# DDS.net
KiCad netlist of a schematic drawn in Altium Designer
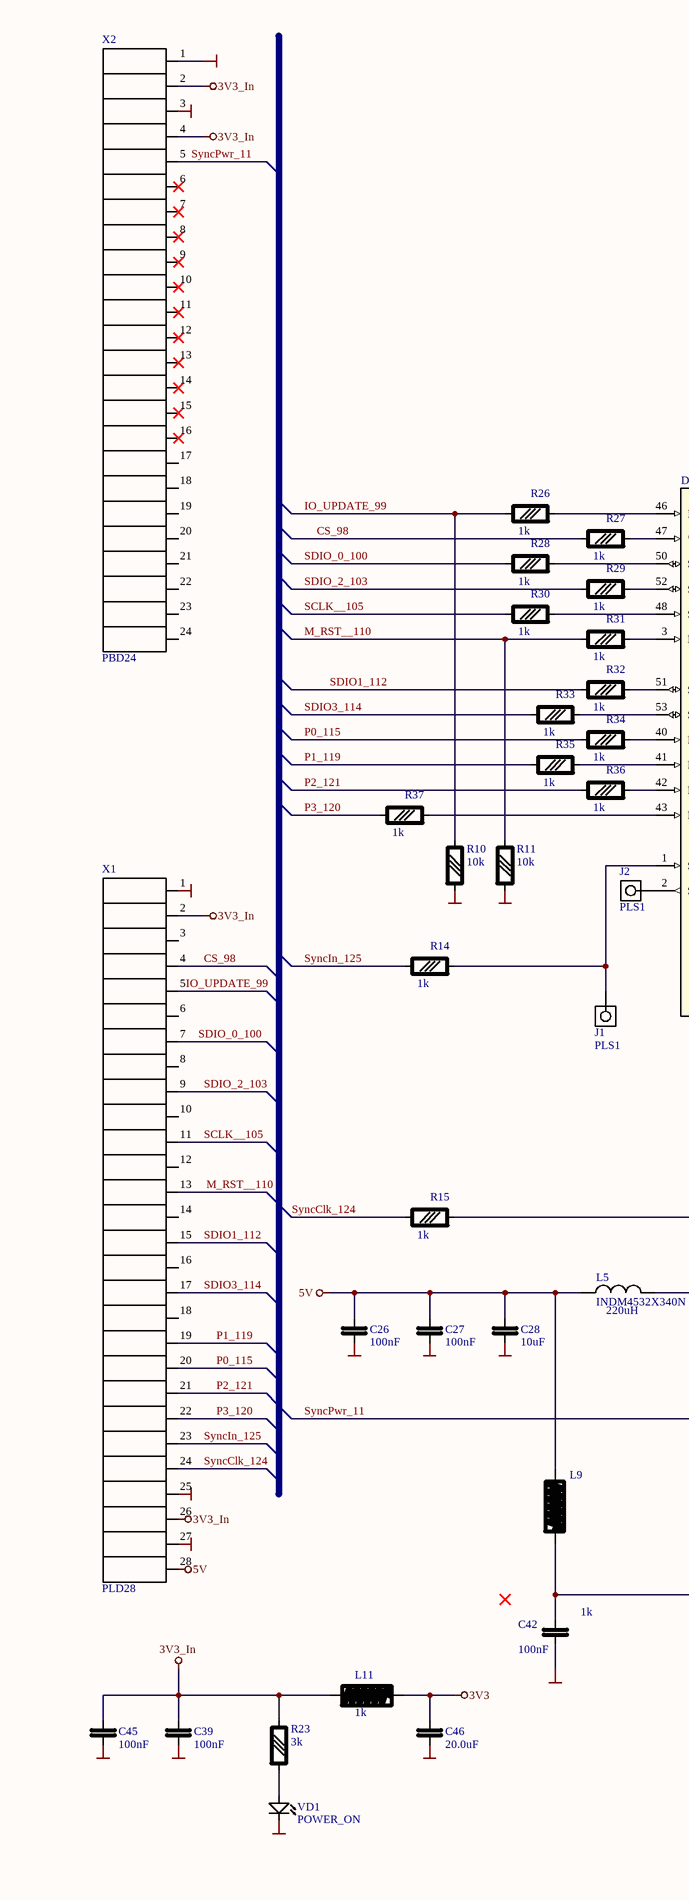
[diagram p0: DDS.SchDoc, left]
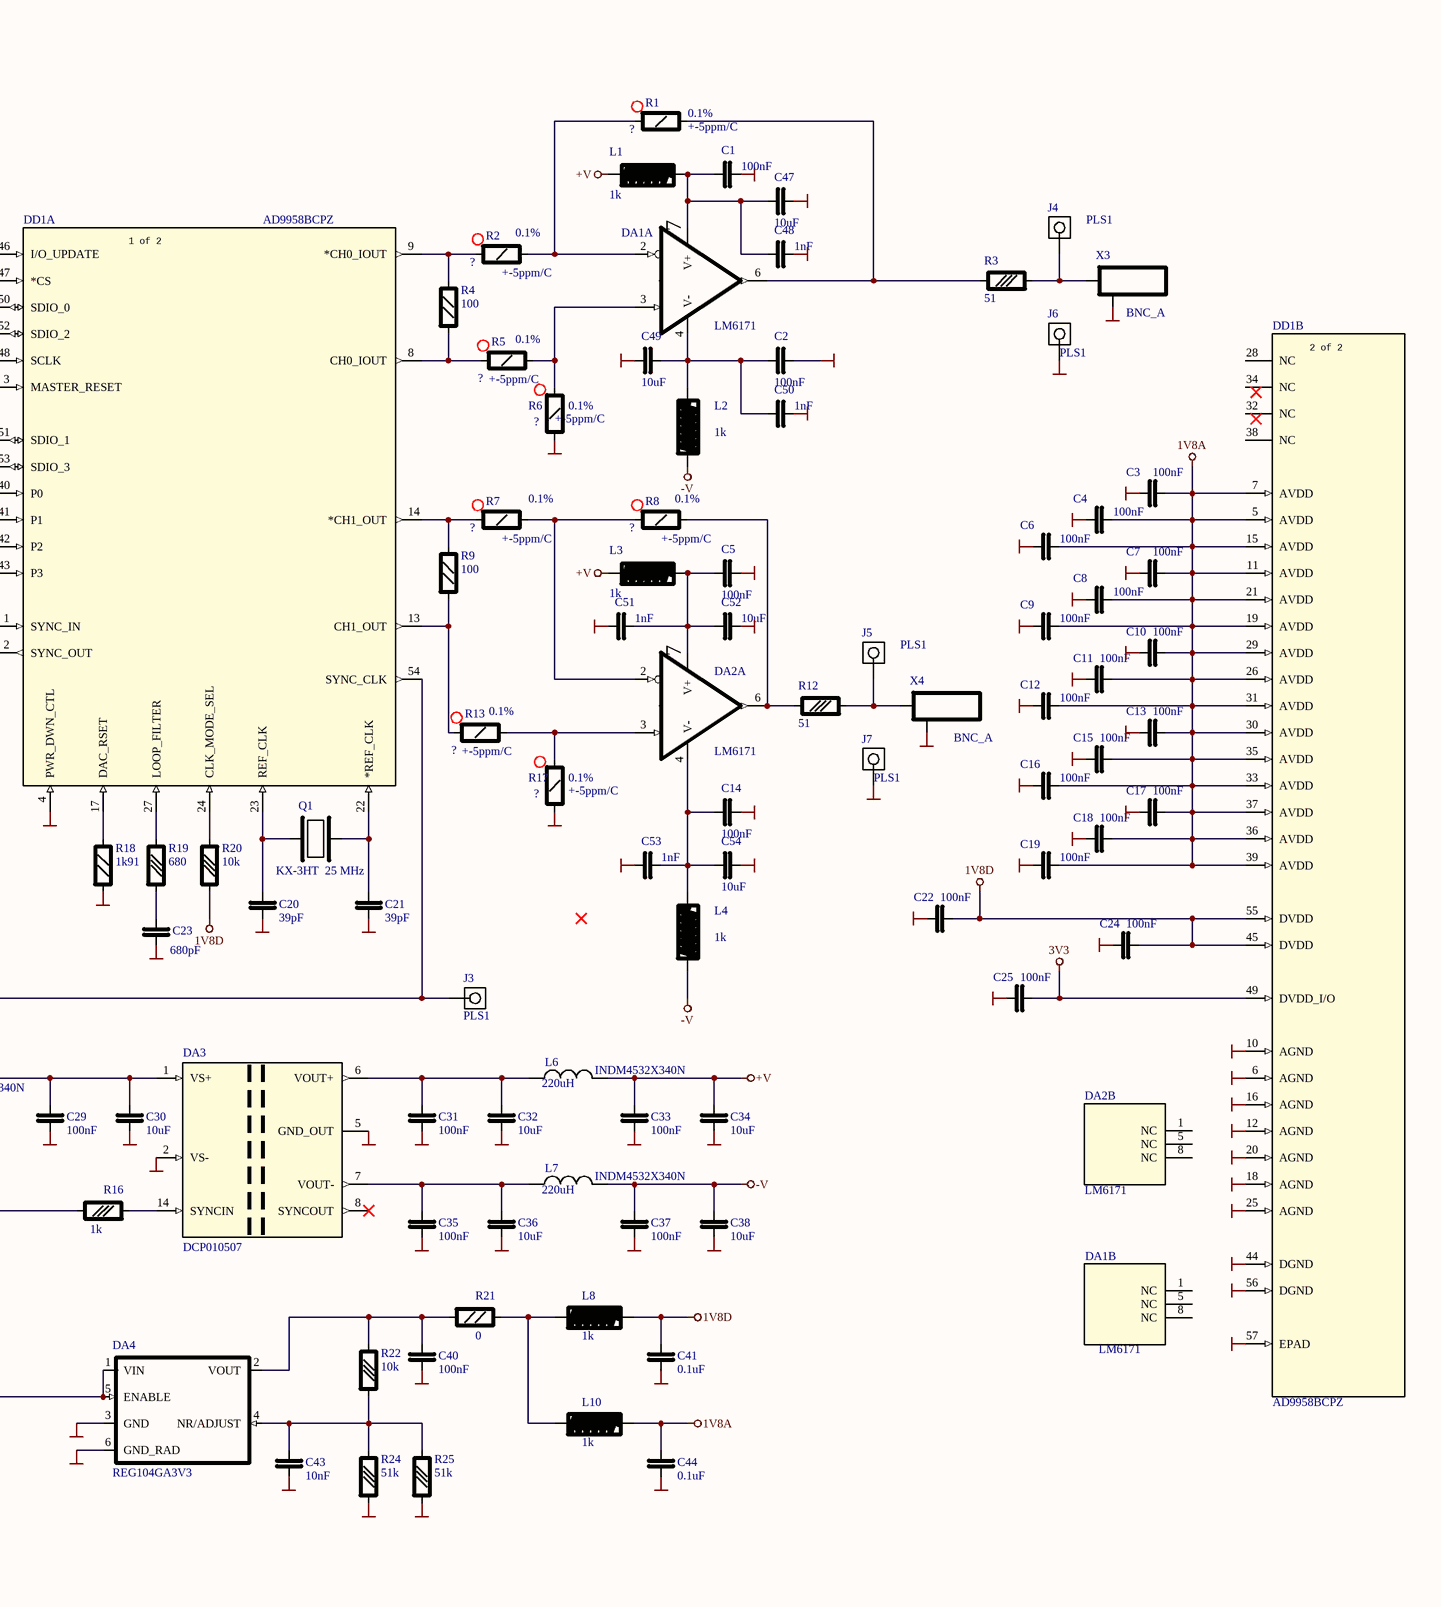
[diagram p1: DDS.SchDoc, right]

(export (version "E")
  (design (tool "Eeschema 10.0.6"))
  (components
    (comp (ref "C1")
      (value "100nF")
      (footprint "CAPC1608X87N")
      (description "Чип конденсатор 0603")
      (fields (field (name "VOLTAGE") "50V"))
      (libsource (lib "iL04_22") (part "C0603"))
    )
    (comp (ref "C2")
      (value "100nF")
      (footprint "CAPC1608X87N")
      (description "Чип конденсатор 0603")
      (fields (field (name "VOLTAGE") "50V"))
      (libsource (lib "iL04_22") (part "C0603"))
    )
    (comp (ref "C3")
      (value "100nF")
      (footprint "CAPC1608X87N")
      (description "Чип конденсатор 0603")
      (fields (field (name "VOLTAGE") "50V"))
      (libsource (lib "iL04_22") (part "C0603"))
    )
    (comp (ref "C4")
      (value "100nF")
      (footprint "CAPC1608X87N")
      (description "Чип конденсатор 0603")
      (fields (field (name "VOLTAGE") "50V"))
      (libsource (lib "iL04_22") (part "C0603"))
    )
    (comp (ref "C5")
      (value "100nF")
      (footprint "CAPC1608X87N")
      (description "Чип конденсатор 0603")
      (fields (field (name "VOLTAGE") "50V"))
      (libsource (lib "iL04_22") (part "C0603"))
    )
    (comp (ref "C6")
      (value "100nF")
      (footprint "CAPC1608X87N")
      (description "Чип конденсатор 0603")
      (fields (field (name "VOLTAGE") "50V"))
      (libsource (lib "iL04_22") (part "C0603"))
    )
    (comp (ref "C7")
      (value "100nF")
      (footprint "CAPC1608X87N")
      (description "Чип конденсатор 0603")
      (fields (field (name "VOLTAGE") "50V"))
      (libsource (lib "iL04_22") (part "C0603"))
    )
    (comp (ref "C8")
      (value "100nF")
      (footprint "CAPC1608X87N")
      (description "Чип конденсатор 0603")
      (fields (field (name "VOLTAGE") "50V"))
      (libsource (lib "iL04_22") (part "C0603"))
    )
    (comp (ref "C9")
      (value "100nF")
      (footprint "CAPC1608X87N")
      (description "Чип конденсатор 0603")
      (fields (field (name "VOLTAGE") "50V"))
      (libsource (lib "iL04_22") (part "C0603"))
    )
    (comp (ref "C10")
      (value "100nF")
      (footprint "CAPC1608X87N")
      (description "Чип конденсатор 0603")
      (fields (field (name "VOLTAGE") "50V"))
      (libsource (lib "iL04_22") (part "C0603"))
    )
    (comp (ref "C11")
      (value "100nF")
      (footprint "CAPC1608X87N")
      (description "Чип конденсатор 0603")
      (fields (field (name "VOLTAGE") "50V"))
      (libsource (lib "iL04_22") (part "C0603"))
    )
    (comp (ref "C12")
      (value "100nF")
      (footprint "CAPC1608X87N")
      (description "Чип конденсатор 0603")
      (fields (field (name "VOLTAGE") "50V"))
      (libsource (lib "iL04_22") (part "C0603"))
    )
    (comp (ref "C13")
      (value "100nF")
      (footprint "CAPC1608X87N")
      (description "Чип конденсатор 0603")
      (fields (field (name "VOLTAGE") "50V"))
      (libsource (lib "iL04_22") (part "C0603"))
    )
    (comp (ref "C14")
      (value "100nF")
      (footprint "CAPC1608X87N")
      (description "Чип конденсатор 0603")
      (fields (field (name "VOLTAGE") "50V"))
      (libsource (lib "iL04_22") (part "C0603"))
    )
    (comp (ref "C15")
      (value "100nF")
      (footprint "CAPC1608X87N")
      (description "Чип конденсатор 0603")
      (fields (field (name "VOLTAGE") "50V"))
      (libsource (lib "iL04_22") (part "C0603"))
    )
    (comp (ref "C16")
      (value "100nF")
      (footprint "CAPC1608X87N")
      (description "Чип конденсатор 0603")
      (fields (field (name "VOLTAGE") "50V"))
      (libsource (lib "iL04_22") (part "C0603"))
    )
    (comp (ref "C17")
      (value "100nF")
      (footprint "CAPC1608X87N")
      (description "Чип конденсатор 0603")
      (fields (field (name "VOLTAGE") "50V"))
      (libsource (lib "iL04_22") (part "C0603"))
    )
    (comp (ref "C18")
      (value "100nF")
      (footprint "CAPC1608X87N")
      (description "Чип конденсатор 0603")
      (fields (field (name "VOLTAGE") "50V"))
      (libsource (lib "iL04_22") (part "C0603"))
    )
    (comp (ref "C19")
      (value "100nF")
      (footprint "CAPC1608X87N")
      (description "Чип конденсатор 0603")
      (fields (field (name "VOLTAGE") "50V"))
      (libsource (lib "iL04_22") (part "C0603"))
    )
    (comp (ref "C20")
      (value "39pF")
      (footprint "CAPC1608X87N")
      (description "Чип конденсатор 0603")
      (fields (field (name "VOLTAGE") "50V"))
      (libsource (lib "iL04_22") (part "C0603"))
    )
    (comp (ref "C21")
      (value "39pF")
      (footprint "CAPC1608X87N")
      (description "Чип конденсатор 0603")
      (fields (field (name "VOLTAGE") "50V"))
      (libsource (lib "iL04_22") (part "C0603"))
    )
    (comp (ref "C22")
      (value "100nF")
      (footprint "CAPC1608X87N")
      (description "Чип конденсатор 0603")
      (fields (field (name "VOLTAGE") "50V"))
      (libsource (lib "iL04_22") (part "C0603"))
    )
    (comp (ref "C23")
      (value "680pF")
      (footprint "CAPC1608X87N")
      (description "Чип конденсатор 0603")
      (fields (field (name "VOLTAGE") "50V"))
      (libsource (lib "iL04_22") (part "C0603"))
    )
    (comp (ref "C24")
      (value "100nF")
      (footprint "CAPC1608X87N")
      (description "Чип конденсатор 0603")
      (fields (field (name "VOLTAGE") "50V"))
      (libsource (lib "iL04_22") (part "C0603"))
    )
    (comp (ref "C25")
      (value "100nF")
      (footprint "CAPC1608X87N")
      (description "Чип конденсатор 0603")
      (fields (field (name "VOLTAGE") "50V"))
      (libsource (lib "iL04_22") (part "C0603"))
    )
    (comp (ref "C26")
      (value "100nF")
      (footprint "CAPC1608X87N")
      (description "Чип конденсатор 0603")
      (fields (field (name "VOLTAGE") "50V"))
      (libsource (lib "iL04_22") (part "C0603"))
    )
    (comp (ref "C27")
      (value "100nF")
      (footprint "CAPC1608X87N")
      (description "Чип конденсатор 0603")
      (fields (field (name "VOLTAGE") "50V"))
      (libsource (lib "iL04_22") (part "C0603"))
    )
    (comp (ref "C28")
      (value "10uF")
      (footprint "SMD0805CAP")
      (description "Чип конденсатор 0805")
      (fields (field (name "VOLTAGE") "50V"))
      (libsource (lib "iL04_22") (part "C0805"))
    )
    (comp (ref "C29")
      (value "100nF")
      (footprint "CAPC1608X87N")
      (description "Чип конденсатор 0603")
      (fields (field (name "VOLTAGE") "50V"))
      (libsource (lib "iL04_22") (part "C0603"))
    )
    (comp (ref "C30")
      (value "10uF")
      (footprint "SMD0805CAP")
      (description "Чип конденсатор 0805")
      (fields (field (name "VOLTAGE") "50V"))
      (libsource (lib "iL04_22") (part "C0805"))
    )
    (comp (ref "C31")
      (value "100nF")
      (footprint "CAPC1608X87N")
      (description "Чип конденсатор 0603")
      (fields (field (name "VOLTAGE") "50V"))
      (libsource (lib "iL04_22") (part "C0603"))
    )
    (comp (ref "C32")
      (value "10uF")
      (footprint "SMD0805CAP")
      (description "Чип конденсатор 0805")
      (fields (field (name "VOLTAGE") "50V"))
      (libsource (lib "iL04_22") (part "C0805"))
    )
    (comp (ref "C33")
      (value "100nF")
      (footprint "CAPC1608X87N")
      (description "Чип конденсатор 0603")
      (fields (field (name "VOLTAGE") "50V"))
      (libsource (lib "iL04_22") (part "C0603"))
    )
    (comp (ref "C34")
      (value "10uF")
      (footprint "SMD0805CAP")
      (description "Чип конденсатор 0805")
      (fields (field (name "VOLTAGE") "50V"))
      (libsource (lib "iL04_22") (part "C0805"))
    )
    (comp (ref "C35")
      (value "100nF")
      (footprint "CAPC1608X87N")
      (description "Чип конденсатор 0603")
      (fields (field (name "VOLTAGE") "50V"))
      (libsource (lib "iL04_22") (part "C0603"))
    )
    (comp (ref "C36")
      (value "10uF")
      (footprint "SMD0805CAP")
      (description "Чип конденсатор 0805")
      (fields (field (name "VOLTAGE") "50V"))
      (libsource (lib "iL04_22") (part "C0805"))
    )
    (comp (ref "C37")
      (value "100nF")
      (footprint "CAPC1608X87N")
      (description "Чип конденсатор 0603")
      (fields (field (name "VOLTAGE") "50V"))
      (libsource (lib "iL04_22") (part "C0603"))
    )
    (comp (ref "C38")
      (value "10uF")
      (footprint "SMD0805CAP")
      (description "Чип конденсатор 0805")
      (fields (field (name "VOLTAGE") "50V"))
      (libsource (lib "iL04_22") (part "C0805"))
    )
    (comp (ref "C39")
      (value "100nF")
      (footprint "CAPC1608X87N")
      (description "Чип конденсатор 0603")
      (fields (field (name "VOLTAGE") "50V"))
      (libsource (lib "iL04_22") (part "C0603"))
    )
    (comp (ref "C40")
      (value "100nF")
      (footprint "CAPC1608X87N")
      (description "Чип конденсатор 0603")
      (fields (field (name "VOLTAGE") "50V"))
      (libsource (lib "iL04_22") (part "C0603"))
    )
    (comp (ref "C41")
      (value "0.1uF")
      (footprint "SMD0805CAP")
      (description "Чип конденсатор 0805")
      (fields (field (name "VOLTAGE") "50V"))
      (libsource (lib "iL04_22") (part "C0805"))
    )
    (comp (ref "C42")
      (value "100nF")
      (footprint "CAPC1608X87N")
      (description "Чип конденсатор 0603")
      (fields (field (name "VOLTAGE") "50V"))
      (libsource (lib "iL04_22") (part "C0603"))
    )
    (comp (ref "C43")
      (value "10nF")
      (footprint "CAPC1608X87N")
      (description "Чип конденсатор 0603")
      (fields (field (name "VOLTAGE") "50V"))
      (libsource (lib "iL04_22") (part "C0603"))
    )
    (comp (ref "C44")
      (value "0.1uF")
      (footprint "SMD0805CAP")
      (description "Чип конденсатор 0805")
      (fields (field (name "VOLTAGE") "50V"))
      (libsource (lib "iL04_22") (part "C0805"))
    )
    (comp (ref "C45")
      (value "100nF")
      (footprint "CAPC1608X87N")
      (description "Чип конденсатор 0603")
      (fields (field (name "VOLTAGE") "50V"))
      (libsource (lib "iL04_22") (part "C0603"))
    )
    (comp (ref "C46")
      (value "20.0uF")
      (footprint "SMD0805CAP")
      (description "Чип конденсатор 0805")
      (fields (field (name "VOLTAGE") "20V"))
      (libsource (lib "iL04_22") (part "C0805"))
    )
    (comp (ref "C47")
      (value "10uF")
      (footprint "CAPC1206")
      (description "Чип конденсатор 0805")
      (fields (field (name "VOLTAGE") "25V"))
      (libsource (lib "iL04_22") (part "C1206"))
    )
    (comp (ref "C48")
      (value "1nF")
      (footprint "CAPC1608X87N")
      (description "Чип конденсатор 0603")
      (fields (field (name "VOLTAGE") "50V"))
      (libsource (lib "iL04_22") (part "C0603"))
    )
    (comp (ref "C49")
      (value "10uF")
      (footprint "CAPC1206")
      (description "Чип конденсатор 0805")
      (fields (field (name "VOLTAGE") "25V"))
      (libsource (lib "iL04_22") (part "C1206"))
    )
    (comp (ref "C50")
      (value "1nF")
      (footprint "CAPC1608X87N")
      (description "Чип конденсатор 0603")
      (fields (field (name "VOLTAGE") "50V"))
      (libsource (lib "iL04_22") (part "C0603"))
    )
    (comp (ref "C51")
      (value "1nF")
      (footprint "CAPC1608X87N")
      (description "Чип конденсатор 0603")
      (fields (field (name "VOLTAGE") "50V"))
      (libsource (lib "iL04_22") (part "C0603"))
    )
    (comp (ref "C52")
      (value "10uF")
      (footprint "CAPC1206")
      (description "Чип конденсатор 0805")
      (fields (field (name "VOLTAGE") "25V"))
      (libsource (lib "iL04_22") (part "C1206"))
    )
    (comp (ref "C53")
      (value "1nF")
      (footprint "CAPC1608X87N")
      (description "Чип конденсатор 0603")
      (fields (field (name "VOLTAGE") "50V"))
      (libsource (lib "iL04_22") (part "C0603"))
    )
    (comp (ref "C54")
      (value "10uF")
      (footprint "CAPC1206")
      (description "Чип конденсатор 0805")
      (fields (field (name "VOLTAGE") "25V"))
      (libsource (lib "iL04_22") (part "C1206"))
    )
    (comp (ref "DA1")
      (value "LM6171")
      (footprint "DIP8-300")
      (description "No Description Available")
      (fields
        (field (name "MANUFACTURER_PART_NUMBER") "LM6171BIN/NOPB")
        (field (name "MANUFACTURER") "Texas Instruments")
      )
      (libsource (lib "SL04_22F") (part "LM6171"))
    )
    (comp (ref "DA2")
      (value "LM6171")
      (footprint "DIP8-300")
      (description "No Description Available")
      (fields
        (field (name "MANUFACTURER_PART_NUMBER") "LM6171BIN/NOPB")
        (field (name "MANUFACTURER") "Texas Instruments")
      )
      (libsource (lib "SL04_22F") (part "LM6171"))
    )
    (comp (ref "DA3")
      (value "DCP010507")
      (footprint "NVA7")
      (description "DC/DC 5V to isolated +-7V")
      (fields (field (name "COPYRIGHT") "Copyright (C) 2022 Ultra Librarian. All rights reserved."))
      (libsource (lib "SL04_22F") (part "DCP010507"))
    )
    (comp (ref "DA4")
      (value "REG104GA3V3")
      (footprint "SOT223_6-127")
      (description "Positive LDO Linear stabilizer")
      (libsource (lib "SL04_22F") (part "REG104GA"))
    )
    (comp (ref "DD1")
      (value "AD9958BCPZ")
      (footprint "CP_56_1_ADI-M")
      (description "2х канальный   500 MSpS  DDS")
      (fields (field (name "VOLTAGE") "Core:1V8 IO:3V3"))
      (libsource (lib "SL04_22F") (part "AD9958BCPZ"))
    )
    (comp (ref "J1")
      (value "PLS1")
      (footprint "PLS1")
      (description "Штырь PLS1")
      (libsource (lib "iL04_22") (part "PLS1"))
    )
    (comp (ref "J2")
      (value "PLS1")
      (footprint "PLS1")
      (description "Штырь PLS1")
      (libsource (lib "iL04_22") (part "PLS1"))
    )
    (comp (ref "J3")
      (value "PLS1")
      (footprint "PLS1")
      (description "Штырь PLS1")
      (libsource (lib "iL04_22") (part "PLS1"))
    )
    (comp (ref "J4")
      (value "PLS1")
      (footprint "PLS1")
      (description "Штырь PLS1")
      (libsource (lib "iL04_22") (part "PLS1"))
    )
    (comp (ref "J5")
      (value "PLS1")
      (footprint "PLS1")
      (description "Штырь PLS1")
      (libsource (lib "iL04_22") (part "PLS1"))
    )
    (comp (ref "J6")
      (value "PLS1")
      (footprint "PLS1")
      (description "Штырь PLS1")
      (libsource (lib "iL04_22") (part "PLS1"))
    )
    (comp (ref "J7")
      (value "PLS1")
      (footprint "PLS1")
      (description "Штырь PLS1")
      (libsource (lib "iL04_22") (part "PLS1"))
    )
    (comp (ref "L1")
      (value "1k")
      (footprint "RESC2012X50N")
      (description "SMD Ferrite bead 0805")
      (libsource (lib "iL04_22") (part "BLM21"))
    )
    (comp (ref "L2")
      (value "1k")
      (footprint "RESC2012X50N")
      (description "SMD Ferrite bead 0805")
      (libsource (lib "") (part "BLM21_1"))
    )
    (comp (ref "L3")
      (value "1k")
      (footprint "RESC2012X50N")
      (description "SMD Ferrite bead 0805")
      (libsource (lib "iL04_22") (part "BLM21"))
    )
    (comp (ref "L4")
      (value "1k")
      (footprint "RESC2012X50N")
      (description "SMD Ferrite bead 0805")
      (libsource (lib "") (part "BLM21_1"))
    )
    (comp (ref "L5")
      (value "INDM4532X340N")
      (footprint "INDM4532X340N")
      (description "SMD Дроссель")
      (fields (field (name "INDUCTANCE") "220uH"))
      (libsource (lib "iL04_22") (part "INDM4532X340N"))
    )
    (comp (ref "L6")
      (value "INDM4532X340N")
      (footprint "INDM4532X340N")
      (description "SMD Дроссель")
      (fields (field (name "INDUCTANCE") "220uH"))
      (libsource (lib "iL04_22") (part "INDM4532X340N"))
    )
    (comp (ref "L7")
      (value "INDM4532X340N")
      (footprint "INDM4532X340N")
      (description "SMD Дроссель")
      (fields (field (name "INDUCTANCE") "220uH"))
      (libsource (lib "iL04_22") (part "INDM4532X340N"))
    )
    (comp (ref "L8")
      (value "1k")
      (footprint "RESC2012X50N")
      (description "SMD Ferrite bead 0805")
      (libsource (lib "iL04_22") (part "BLM21"))
    )
    (comp (ref "L9")
      (value "1k")
      (footprint "RESC2012X50N")
      (description "SMD Ferrite bead 0805")
      (libsource (lib "") (part "BLM21_2"))
    )
    (comp (ref "L10")
      (value "1k")
      (footprint "RESC2012X50N")
      (description "SMD Ferrite bead 0805")
      (libsource (lib "iL04_22") (part "BLM21"))
    )
    (comp (ref "L11")
      (value "1k")
      (footprint "RESC2012X50N")
      (description "SMD Ferrite bead 0805")
      (libsource (lib "iL04_22") (part "BLM21"))
    )
    (comp (ref "Q1")
      (value "KX-3HT  25 MHz")
      (footprint "HC49_S")
      (description "Резонатор кварцевый")
      (libsource (lib "iL04_22") (part "KX-3HT"))
    )
    (comp (ref "R1")
      (value "?")
      (footprint "RES_VISHAY_CMF60")
      (description "Чип резистор 1206")
      (fields (field (name "TOLERANCE") "0.1%") (field (name "TC") "+-5ppm/C"))
      (libsource (lib "iL04_22") (part "S2-29"))
    )
    (comp (ref "R2")
      (value "?")
      (footprint "RES_VISHAY_CMF60")
      (description "Чип резистор 1206")
      (fields (field (name "TOLERANCE") "0.1%") (field (name "TC") "+-5ppm/C"))
      (libsource (lib "iL04_22") (part "S2-29"))
    )
    (comp (ref "R3")
      (value "51")
      (footprint "RESC1608X64N")
      (description "Чип резистор 0603")
      (fields (field (name "TOLERANCE") "5%"))
      (libsource (lib "iL04_22") (part "R0603"))
    )
    (comp (ref "R4")
      (value "100")
      (footprint "SMD0805RES")
      (description "Чип резистор 0805")
      (fields (field (name "TOLERANCE") "5%"))
      (libsource (lib "iL04_22") (part "R0805"))
    )
    (comp (ref "R5")
      (value "?")
      (footprint "RES_VISHAY_CMF60")
      (description "Чип резистор 1206")
      (fields (field (name "TOLERANCE") "0.1%") (field (name "TC") "+-5ppm/C"))
      (libsource (lib "iL04_22") (part "S2-29"))
    )
    (comp (ref "R6")
      (value "?")
      (footprint "RES_VISHAY_CMF60")
      (description "Чип резистор 1206")
      (fields (field (name "TOLERANCE") "0.1%") (field (name "TC") "+-5ppm/C"))
      (libsource (lib "") (part "S2-29_1"))
    )
    (comp (ref "R7")
      (value "?")
      (footprint "RES_VISHAY_CMF60")
      (description "Чип резистор 1206")
      (fields (field (name "TOLERANCE") "0.1%") (field (name "TC") "+-5ppm/C"))
      (libsource (lib "iL04_22") (part "S2-29"))
    )
    (comp (ref "R8")
      (value "?")
      (footprint "RES_VISHAY_CMF60")
      (description "Чип резистор 1206")
      (fields (field (name "TOLERANCE") "0.1%") (field (name "TC") "+-5ppm/C"))
      (libsource (lib "iL04_22") (part "S2-29"))
    )
    (comp (ref "R9")
      (value "100")
      (footprint "SMD0805RES")
      (description "Чип резистор 0805")
      (fields (field (name "TOLERANCE") "5%"))
      (libsource (lib "iL04_22") (part "R0805"))
    )
    (comp (ref "R10")
      (value "10k")
      (footprint "RESC1608X64N")
      (description "Чип резистор 0603")
      (fields (field (name "TOLERANCE") "5%"))
      (libsource (lib "iL04_22") (part "R0603"))
    )
    (comp (ref "R11")
      (value "10k")
      (footprint "RESC1608X64N")
      (description "Чип резистор 0603")
      (fields (field (name "TOLERANCE") "5%"))
      (libsource (lib "iL04_22") (part "R0603"))
    )
    (comp (ref "R12")
      (value "51")
      (footprint "RESC1608X64N")
      (description "Чип резистор 0603")
      (fields (field (name "TOLERANCE") "5%"))
      (libsource (lib "iL04_22") (part "R0603"))
    )
    (comp (ref "R13")
      (value "?")
      (footprint "RES_VISHAY_CMF60")
      (description "Чип резистор 1206")
      (fields (field (name "TOLERANCE") "0.1%") (field (name "TC") "+-5ppm/C"))
      (libsource (lib "iL04_22") (part "S2-29"))
    )
    (comp (ref "R14")
      (value "1k")
      (footprint "RESC1608X64N")
      (description "Чип резистор 0603")
      (fields (field (name "TOLERANCE") "5%"))
      (libsource (lib "iL04_22") (part "R0603"))
    )
    (comp (ref "R15")
      (value "1k")
      (footprint "RESC1608X64N")
      (description "Чип резистор 0603")
      (fields (field (name "TOLERANCE") "5%"))
      (libsource (lib "iL04_22") (part "R0603"))
    )
    (comp (ref "R16")
      (value "1k")
      (footprint "RESC1608X64N")
      (description "Чип резистор 0603")
      (fields (field (name "TOLERANCE") "5%"))
      (libsource (lib "iL04_22") (part "R0603"))
    )
    (comp (ref "R17")
      (value "?")
      (footprint "RES_VISHAY_CMF60")
      (description "Чип резистор 1206")
      (fields (field (name "TOLERANCE") "0.1%") (field (name "TC") "+-5ppm/C"))
      (libsource (lib "") (part "S2-29_1"))
    )
    (comp (ref "R18")
      (value "1k91")
      (footprint "SMD0805RES")
      (description "Чип резистор 0805")
      (fields (field (name "TOLERANCE") "5%"))
      (libsource (lib "iL04_22") (part "R0805"))
    )
    (comp (ref "R19")
      (value "680")
      (footprint "RESC1608X64N")
      (description "Чип резистор 0603")
      (fields (field (name "TOLERANCE") "5%"))
      (libsource (lib "iL04_22") (part "R0603"))
    )
    (comp (ref "R20")
      (value "10k")
      (footprint "RESC1608X64N")
      (description "Чип резистор 0603")
      (fields (field (name "TOLERANCE") "5%"))
      (libsource (lib "iL04_22") (part "R0603"))
    )
    (comp (ref "R21")
      (value "0")
      (footprint "SMD0805RES")
      (description "Чип резистор 0805")
      (fields (field (name "TOLERANCE") "5%"))
      (libsource (lib "iL04_22") (part "R0805"))
    )
    (comp (ref "R22")
      (value "10k")
      (footprint "RESC1608X64N")
      (description "Чип резистор 0603")
      (fields (field (name "TOLERANCE") "5%"))
      (libsource (lib "iL04_22") (part "R0603"))
    )
    (comp (ref "R23")
      (value "3k")
      (footprint "RESC1608X64N")
      (description "Чип резистор 0603")
      (fields (field (name "TOLERANCE") "5%"))
      (libsource (lib "iL04_22") (part "R0603"))
    )
    (comp (ref "R24")
      (value "51k")
      (footprint "RESC1608X64N")
      (description "Чип резистор 0603")
      (fields (field (name "TOLERANCE") "5%"))
      (libsource (lib "iL04_22") (part "R0603"))
    )
    (comp (ref "R25")
      (value "51k")
      (footprint "RESC1608X64N")
      (description "Чип резистор 0603")
      (fields (field (name "TOLERANCE") "5%"))
      (libsource (lib "iL04_22") (part "R0603"))
    )
    (comp (ref "R26")
      (value "1k")
      (footprint "RESC1608X64N")
      (description "Чип резистор 0603")
      (fields (field (name "TOLERANCE") "5%"))
      (libsource (lib "iL04_22") (part "R0603"))
    )
    (comp (ref "R27")
      (value "1k")
      (footprint "RESC1608X64N")
      (description "Чип резистор 0603")
      (fields (field (name "TOLERANCE") "5%"))
      (libsource (lib "iL04_22") (part "R0603"))
    )
    (comp (ref "R28")
      (value "1k")
      (footprint "RESC1608X64N")
      (description "Чип резистор 0603")
      (fields (field (name "TOLERANCE") "5%"))
      (libsource (lib "iL04_22") (part "R0603"))
    )
    (comp (ref "R29")
      (value "1k")
      (footprint "RESC1608X64N")
      (description "Чип резистор 0603")
      (fields (field (name "TOLERANCE") "5%"))
      (libsource (lib "iL04_22") (part "R0603"))
    )
    (comp (ref "R30")
      (value "1k")
      (footprint "RESC1608X64N")
      (description "Чип резистор 0603")
      (fields (field (name "TOLERANCE") "5%"))
      (libsource (lib "iL04_22") (part "R0603"))
    )
    (comp (ref "R31")
      (value "1k")
      (footprint "RESC1608X64N")
      (description "Чип резистор 0603")
      (fields (field (name "TOLERANCE") "5%"))
      (libsource (lib "iL04_22") (part "R0603"))
    )
    (comp (ref "R32")
      (value "1k")
      (footprint "RESC1608X64N")
      (description "Чип резистор 0603")
      (fields (field (name "TOLERANCE") "5%"))
      (libsource (lib "iL04_22") (part "R0603"))
    )
    (comp (ref "R33")
      (value "1k")
      (footprint "RESC1608X64N")
      (description "Чип резистор 0603")
      (fields (field (name "TOLERANCE") "5%"))
      (libsource (lib "iL04_22") (part "R0603"))
    )
    (comp (ref "R34")
      (value "1k")
      (footprint "RESC1608X64N")
      (description "Чип резистор 0603")
      (fields (field (name "TOLERANCE") "5%"))
      (libsource (lib "iL04_22") (part "R0603"))
    )
    (comp (ref "R35")
      (value "1k")
      (footprint "RESC1608X64N")
      (description "Чип резистор 0603")
      (fields (field (name "TOLERANCE") "5%"))
      (libsource (lib "iL04_22") (part "R0603"))
    )
    (comp (ref "R36")
      (value "1k")
      (footprint "RESC1608X64N")
      (description "Чип резистор 0603")
      (fields (field (name "TOLERANCE") "5%"))
      (libsource (lib "iL04_22") (part "R0603"))
    )
    (comp (ref "R37")
      (value "1k")
      (footprint "RESC1608X64N")
      (description "Чип резистор 0603")
      (fields (field (name "TOLERANCE") "5%"))
      (libsource (lib "iL04_22") (part "R0603"))
    )
    (comp (ref "VD1")
      (value "POWER_ON")
      (footprint "LED0603")
      (description "Чип светодиод 0603")
      (libsource (lib "iL04_22") (part "LED0603"))
    )
    (comp (ref "X1")
      (value "PLD28")
      (footprint "PLD28")
      (description "Вилка  PLD 28/2.54")
      (libsource (lib "SL04_22F") (part "PLD28"))
    )
    (comp (ref "X2")
      (value "PBD24")
      (footprint "PBD24")
      (description "Розетка  PBD 24/2.54")
      (libsource (lib "SL04_22F") (part "PBD24"))
    )
    (comp (ref "X3")
      (value "BNC_A")
      (footprint "TYCO_1-1337542-0")
      (description "BNC розетка")
      (fields (field (name "PARTNUM") "TYCO_1-1337542-0"))
      (libsource (lib "iL04_22") (part "BNC_A"))
    )
    (comp (ref "X4")
      (value "BNC_A")
      (footprint "TYCO_1-1337542-0")
      (description "BNC розетка")
      (fields (field (name "PARTNUM") "TYCO_1-1337542-0"))
      (libsource (lib "iL04_22") (part "BNC_A"))
    )
  )
  (nets
    (net (code "1") (name "+V") (class "Default")
      (node (ref "C33") (pin "2") (pinfunction "2_2") (pintype "passive"))
      (node (ref "C34") (pin "2") (pinfunction "2_2") (pintype "passive"))
      (node (ref "L1") (pin "1") (pinfunction "1_1") (pintype "passive"))
      (node (ref "L3") (pin "1") (pinfunction "1_1") (pintype "passive"))
      (node (ref "L6") (pin "2") (pinfunction "2_2") (pintype "passive"))
    )
    (net (code "2") (name "-V") (class "Default")
      (node (ref "C37") (pin "2") (pinfunction "2_2") (pintype "passive"))
      (node (ref "C38") (pin "2") (pinfunction "2_2") (pintype "passive"))
      (node (ref "L2") (pin "1") (pinfunction "1_1") (pintype "passive"))
      (node (ref "L4") (pin "1") (pinfunction "1_1") (pintype "passive"))
      (node (ref "L7") (pin "2") (pinfunction "2_2") (pintype "passive"))
    )
    (net (code "3") (name "/CS_98") (class "Default")
      (node (ref "R27") (pin "2") (pinfunction "2_2") (pintype "passive"))
      (node (ref "X1") (pin "4") (pinfunction "4_4") (pintype "passive"))
    )
    (net (code "4") (name "/IO_UPDATE_99") (class "Default")
      (node (ref "R10") (pin "2") (pinfunction "2_2") (pintype "passive"))
      (node (ref "R26") (pin "2") (pinfunction "2_2") (pintype "passive"))
      (node (ref "X1") (pin "5") (pinfunction "5_5") (pintype "passive"))
    )
    (net (code "5") (name "/M_RST__110") (class "Default")
      (node (ref "R11") (pin "2") (pinfunction "2_2") (pintype "passive"))
      (node (ref "R31") (pin "2") (pinfunction "2_2") (pintype "passive"))
      (node (ref "X1") (pin "13") (pinfunction "13_13") (pintype "passive"))
    )
    (net (code "6") (name "/P0_115") (class "Default")
      (node (ref "R34") (pin "2") (pinfunction "2_2") (pintype "passive"))
      (node (ref "X1") (pin "20") (pinfunction "20_20") (pintype "passive"))
    )
    (net (code "7") (name "/P1_119") (class "Default")
      (node (ref "R35") (pin "2") (pinfunction "2_2") (pintype "passive"))
      (node (ref "X1") (pin "19") (pinfunction "19_19") (pintype "passive"))
    )
    (net (code "8") (name "/P2_121") (class "Default")
      (node (ref "R36") (pin "2") (pinfunction "2_2") (pintype "passive"))
      (node (ref "X1") (pin "21") (pinfunction "21_21") (pintype "passive"))
    )
    (net (code "9") (name "/P3_120") (class "Default")
      (node (ref "R37") (pin "2") (pinfunction "2_2") (pintype "passive"))
      (node (ref "X1") (pin "22") (pinfunction "22_22") (pintype "passive"))
    )
    (net (code "10") (name "/SCLK__105") (class "Default")
      (node (ref "R30") (pin "2") (pinfunction "2_2") (pintype "passive"))
      (node (ref "X1") (pin "11") (pinfunction "11_11") (pintype "passive"))
    )
    (net (code "11") (name "/SDIO1_112") (class "Default")
      (node (ref "R32") (pin "2") (pinfunction "2_2") (pintype "passive"))
      (node (ref "X1") (pin "15") (pinfunction "15_15") (pintype "passive"))
    )
    (net (code "12") (name "/SDIO3_114") (class "Default")
      (node (ref "R33") (pin "2") (pinfunction "2_2") (pintype "passive"))
      (node (ref "X1") (pin "17") (pinfunction "17_17") (pintype "passive"))
    )
    (net (code "13") (name "/SDIO_0_100") (class "Default")
      (node (ref "R28") (pin "2") (pinfunction "2_2") (pintype "passive"))
      (node (ref "X1") (pin "7") (pinfunction "7_7") (pintype "passive"))
    )
    (net (code "14") (name "/SDIO_2_103") (class "Default")
      (node (ref "R29") (pin "2") (pinfunction "2_2") (pintype "passive"))
      (node (ref "X1") (pin "9") (pinfunction "9_9") (pintype "passive"))
    )
    (net (code "15") (name "/SyncClk_124") (class "Default")
      (node (ref "R15") (pin "2") (pinfunction "2_2") (pintype "passive"))
      (node (ref "X1") (pin "24") (pinfunction "24_24") (pintype "passive"))
    )
    (net (code "16") (name "/SyncIn_125") (class "Default")
      (node (ref "R14") (pin "2") (pinfunction "2_2") (pintype "passive"))
      (node (ref "X1") (pin "23") (pinfunction "23_23") (pintype "passive"))
    )
    (net (code "17") (name "/SyncPwr_11") (class "Default")
      (node (ref "R16") (pin "2") (pinfunction "2_2") (pintype "passive"))
      (node (ref "X2") (pin "5") (pinfunction "5_5") (pintype "passive"))
    )
    (net (code "18") (name "1V8A") (class "Default")
      (node (ref "C10") (pin "1") (pinfunction "1_1") (pintype "passive"))
      (node (ref "C11") (pin "1") (pinfunction "1_1") (pintype "passive"))
      (node (ref "C12") (pin "1") (pinfunction "1_1") (pintype "passive"))
      (node (ref "C13") (pin "1") (pinfunction "1_1") (pintype "passive"))
      (node (ref "C15") (pin "1") (pinfunction "1_1") (pintype "passive"))
      (node (ref "C16") (pin "1") (pinfunction "1_1") (pintype "passive"))
      (node (ref "C17") (pin "1") (pinfunction "1_1") (pintype "passive"))
      (node (ref "C18") (pin "1") (pinfunction "1_1") (pintype "passive"))
      (node (ref "C19") (pin "1") (pinfunction "1_1") (pintype "passive"))
      (node (ref "C3") (pin "1") (pinfunction "1_1") (pintype "passive"))
      (node (ref "C4") (pin "1") (pinfunction "1_1") (pintype "passive"))
      (node (ref "C44") (pin "2") (pinfunction "2_2") (pintype "passive"))
      (node (ref "C6") (pin "1") (pinfunction "1_1") (pintype "passive"))
      (node (ref "C7") (pin "1") (pinfunction "1_1") (pintype "passive"))
      (node (ref "C8") (pin "1") (pinfunction "1_1") (pintype "passive"))
      (node (ref "C9") (pin "1") (pinfunction "1_1") (pintype "passive"))
      (node (ref "DD1") (pin "11") (pinfunction "AVDD_11") (pintype "input"))
      (node (ref "DD1") (pin "15") (pinfunction "AVDD_15") (pintype "input"))
      (node (ref "DD1") (pin "19") (pinfunction "AVDD_19") (pintype "input"))
      (node (ref "DD1") (pin "21") (pinfunction "AVDD_21") (pintype "input"))
      (node (ref "DD1") (pin "26") (pinfunction "AVDD_26") (pintype "input"))
      (node (ref "DD1") (pin "29") (pinfunction "AVDD_29") (pintype "input"))
      (node (ref "DD1") (pin "30") (pinfunction "AVDD_30") (pintype "input"))
      (node (ref "DD1") (pin "31") (pinfunction "AVDD_31") (pintype "input"))
      (node (ref "DD1") (pin "33") (pinfunction "AVDD_33") (pintype "input"))
      (node (ref "DD1") (pin "35") (pinfunction "AVDD_35") (pintype "input"))
      (node (ref "DD1") (pin "36") (pinfunction "AVDD_36") (pintype "input"))
      (node (ref "DD1") (pin "37") (pinfunction "AVDD_37") (pintype "input"))
      (node (ref "DD1") (pin "39") (pinfunction "AVDD_39") (pintype "input"))
      (node (ref "DD1") (pin "5") (pinfunction "AVDD_5") (pintype "input"))
      (node (ref "DD1") (pin "7") (pinfunction "AVDD_7") (pintype "input"))
      (node (ref "L10") (pin "2") (pinfunction "2_2") (pintype "passive"))
    )
    (net (code "19") (name "1V8D") (class "Default")
      (node (ref "C22") (pin "1") (pinfunction "1_1") (pintype "passive"))
      (node (ref "C24") (pin "1") (pinfunction "1_1") (pintype "passive"))
      (node (ref "C41") (pin "2") (pinfunction "2_2") (pintype "passive"))
      (node (ref "DD1") (pin "45") (pinfunction "DVDD_45") (pintype "input"))
      (node (ref "DD1") (pin "55") (pinfunction "DVDD_55") (pintype "input"))
      (node (ref "L8") (pin "2") (pinfunction "2_2") (pintype "passive"))
      (node (ref "R20") (pin "2") (pinfunction "2_2") (pintype "passive"))
    )
    (net (code "20") (name "3V3") (class "Default")
      (node (ref "C25") (pin "1") (pinfunction "1_1") (pintype "passive"))
      (node (ref "C46") (pin "2") (pinfunction "2_2") (pintype "passive"))
      (node (ref "DD1") (pin "49") (pinfunction "DVDD_I/O_49") (pintype "input"))
      (node (ref "L11") (pin "2") (pinfunction "2_2") (pintype "passive"))
    )
    (net (code "21") (name "3V3_In") (class "Default")
      (node (ref "C39") (pin "2") (pinfunction "2_2") (pintype "passive"))
      (node (ref "C45") (pin "2") (pinfunction "2_2") (pintype "passive"))
      (node (ref "L11") (pin "1") (pinfunction "1_1") (pintype "passive"))
      (node (ref "R23") (pin "2") (pinfunction "2_2") (pintype "passive"))
      (node (ref "X1") (pin "2") (pinfunction "2_2") (pintype "passive"))
      (node (ref "X1") (pin "26") (pinfunction "26_26") (pintype "passive"))
      (node (ref "X2") (pin "2") (pinfunction "2_2") (pintype "passive"))
      (node (ref "X2") (pin "4") (pinfunction "4_4") (pintype "passive"))
    )
    (net (code "22") (name "5V") (class "Default")
      (node (ref "C26") (pin "2") (pinfunction "2_2") (pintype "passive"))
      (node (ref "C27") (pin "2") (pinfunction "2_2") (pintype "passive"))
      (node (ref "C28") (pin "2") (pinfunction "2_2") (pintype "passive"))
      (node (ref "L5") (pin "1") (pinfunction "1_1") (pintype "passive"))
      (node (ref "L9") (pin "1") (pinfunction "1_1") (pintype "passive"))
      (node (ref "X1") (pin "28") (pinfunction "28_28") (pintype "passive"))
    )
    (net (code "23") (name "GND") (class "Default")
      (node (ref "C1") (pin "1") (pinfunction "1_1") (pintype "passive"))
      (node (ref "C10") (pin "2") (pinfunction "2_2") (pintype "passive"))
      (node (ref "C11") (pin "2") (pinfunction "2_2") (pintype "passive"))
      (node (ref "C12") (pin "2") (pinfunction "2_2") (pintype "passive"))
      (node (ref "C13") (pin "2") (pinfunction "2_2") (pintype "passive"))
      (node (ref "C14") (pin "1") (pinfunction "1_1") (pintype "passive"))
      (node (ref "C15") (pin "2") (pinfunction "2_2") (pintype "passive"))
      (node (ref "C16") (pin "2") (pinfunction "2_2") (pintype "passive"))
      (node (ref "C17") (pin "2") (pinfunction "2_2") (pintype "passive"))
      (node (ref "C18") (pin "2") (pinfunction "2_2") (pintype "passive"))
      (node (ref "C19") (pin "2") (pinfunction "2_2") (pintype "passive"))
      (node (ref "C2") (pin "1") (pinfunction "1_1") (pintype "passive"))
      (node (ref "C20") (pin "1") (pinfunction "1_1") (pintype "passive"))
      (node (ref "C21") (pin "1") (pinfunction "1_1") (pintype "passive"))
      (node (ref "C22") (pin "2") (pinfunction "2_2") (pintype "passive"))
      (node (ref "C23") (pin "1") (pinfunction "1_1") (pintype "passive"))
      (node (ref "C24") (pin "2") (pinfunction "2_2") (pintype "passive"))
      (node (ref "C25") (pin "2") (pinfunction "2_2") (pintype "passive"))
      (node (ref "C26") (pin "1") (pinfunction "1_1") (pintype "passive"))
      (node (ref "C27") (pin "1") (pinfunction "1_1") (pintype "passive"))
      (node (ref "C28") (pin "1") (pinfunction "1_1") (pintype "passive"))
      (node (ref "C29") (pin "1") (pinfunction "1_1") (pintype "passive"))
      (node (ref "C3") (pin "2") (pinfunction "2_2") (pintype "passive"))
      (node (ref "C30") (pin "1") (pinfunction "1_1") (pintype "passive"))
      (node (ref "C31") (pin "1") (pinfunction "1_1") (pintype "passive"))
      (node (ref "C32") (pin "1") (pinfunction "1_1") (pintype "passive"))
      (node (ref "C33") (pin "1") (pinfunction "1_1") (pintype "passive"))
      (node (ref "C34") (pin "1") (pinfunction "1_1") (pintype "passive"))
      (node (ref "C35") (pin "1") (pinfunction "1_1") (pintype "passive"))
      (node (ref "C36") (pin "1") (pinfunction "1_1") (pintype "passive"))
      (node (ref "C37") (pin "1") (pinfunction "1_1") (pintype "passive"))
      (node (ref "C38") (pin "1") (pinfunction "1_1") (pintype "passive"))
      (node (ref "C39") (pin "1") (pinfunction "1_1") (pintype "passive"))
      (node (ref "C4") (pin "2") (pinfunction "2_2") (pintype "passive"))
      (node (ref "C40") (pin "1") (pinfunction "1_1") (pintype "passive"))
      (node (ref "C41") (pin "1") (pinfunction "1_1") (pintype "passive"))
      (node (ref "C42") (pin "1") (pinfunction "1_1") (pintype "passive"))
      (node (ref "C43") (pin "1") (pinfunction "1_1") (pintype "passive"))
      (node (ref "C44") (pin "1") (pinfunction "1_1") (pintype "passive"))
      (node (ref "C45") (pin "1") (pinfunction "1_1") (pintype "passive"))
      (node (ref "C46") (pin "1") (pinfunction "1_1") (pintype "passive"))
      (node (ref "C47") (pin "1") (pinfunction "1_1") (pintype "passive"))
      (node (ref "C48") (pin "1") (pinfunction "1_1") (pintype "passive"))
      (node (ref "C49") (pin "1") (pinfunction "1_1") (pintype "passive"))
      (node (ref "C5") (pin "1") (pinfunction "1_1") (pintype "passive"))
      (node (ref "C50") (pin "1") (pinfunction "1_1") (pintype "passive"))
      (node (ref "C51") (pin "2") (pinfunction "2_2") (pintype "passive"))
      (node (ref "C52") (pin "2") (pinfunction "2_2") (pintype "passive"))
      (node (ref "C53") (pin "2") (pinfunction "2_2") (pintype "passive"))
      (node (ref "C54") (pin "2") (pinfunction "2_2") (pintype "passive"))
      (node (ref "C6") (pin "2") (pinfunction "2_2") (pintype "passive"))
      (node (ref "C7") (pin "2") (pinfunction "2_2") (pintype "passive"))
      (node (ref "C8") (pin "2") (pinfunction "2_2") (pintype "passive"))
      (node (ref "C9") (pin "2") (pinfunction "2_2") (pintype "passive"))
      (node (ref "DA3") (pin "2") (pinfunction "VS-_2") (pintype "input"))
      (node (ref "DA3") (pin "5") (pinfunction "GND_OUT_5") (pintype "power_in"))
      (node (ref "DA4") (pin "3") (pinfunction "GND_3") (pintype "power_in"))
      (node (ref "DA4") (pin "6") (pinfunction "GND_RAD_6") (pintype "power_in"))
      (node (ref "DD1") (pin "10") (pinfunction "AGND_10") (pintype "input"))
      (node (ref "DD1") (pin "12") (pinfunction "AGND_12") (pintype "input"))
      (node (ref "DD1") (pin "16") (pinfunction "AGND_16") (pintype "input"))
      (node (ref "DD1") (pin "18") (pinfunction "AGND_18") (pintype "input"))
      (node (ref "DD1") (pin "20") (pinfunction "AGND_20") (pintype "input"))
      (node (ref "DD1") (pin "25") (pinfunction "AGND_25") (pintype "input"))
      (node (ref "DD1") (pin "4") (pinfunction "PWR_DWN_CTL_4") (pintype "input"))
      (node (ref "DD1") (pin "44") (pinfunction "DGND_44") (pintype "input"))
      (node (ref "DD1") (pin "56") (pinfunction "DGND_56") (pintype "input"))
      (node (ref "DD1") (pin "57") (pinfunction "EPAD_57") (pintype "input"))
      (node (ref "DD1") (pin "6") (pinfunction "AGND_6") (pintype "input"))
      (node (ref "J6") (pin "1") (pinfunction "1_1") (pintype "passive"))
      (node (ref "J7") (pin "1") (pinfunction "1_1") (pintype "passive"))
      (node (ref "R10") (pin "1") (pinfunction "1_1") (pintype "passive"))
      (node (ref "R11") (pin "1") (pinfunction "1_1") (pintype "passive"))
      (node (ref "R17") (pin "2") (pinfunction "2_2") (pintype "passive"))
      (node (ref "R18") (pin "1") (pinfunction "1_1") (pintype "passive"))
      (node (ref "R24") (pin "1") (pinfunction "1_1") (pintype "passive"))
      (node (ref "R25") (pin "1") (pinfunction "1_1") (pintype "passive"))
      (node (ref "R6") (pin "2") (pinfunction "2_2") (pintype "passive"))
      (node (ref "VD1") (pin "1") (pinfunction "Cathode_1") (pintype "passive"))
      (node (ref "X1") (pin "1") (pinfunction "1_1") (pintype "passive"))
      (node (ref "X1") (pin "25") (pinfunction "25_25") (pintype "passive"))
      (node (ref "X1") (pin "27") (pinfunction "27_27") (pintype "passive"))
      (node (ref "X2") (pin "1") (pinfunction "1_1") (pintype "passive"))
      (node (ref "X2") (pin "3") (pinfunction "3_3") (pintype "passive"))
      (node (ref "X3") (pin "2") (pinfunction "2_2") (pintype "passive"))
      (node (ref "X4") (pin "2") (pinfunction "2_2") (pintype "passive"))
    )
    (net (code "24") (name "Net-(C23-Pad2)") (class "Default")
      (node (ref "C23") (pin "2") (pinfunction "2_2") (pintype "passive"))
      (node (ref "R19") (pin "1") (pinfunction "1_1") (pintype "passive"))
    )
    (net (code "25") (name "Net-(DA1A-IN+)") (class "Default")
      (node (ref "DA1") (pin "3") (pinfunction "IN+_3") (pintype "input"))
      (node (ref "R5") (pin "2") (pinfunction "2_2") (pintype "passive"))
      (node (ref "R6") (pin "1") (pinfunction "1_1") (pintype "passive"))
    )
    (net (code "26") (name "Net-(DA1A-IN-)") (class "Default")
      (node (ref "DA1") (pin "2") (pinfunction "IN-_2") (pintype "input"))
      (node (ref "R1") (pin "1") (pinfunction "1_1") (pintype "passive"))
      (node (ref "R2") (pin "2") (pinfunction "2_2") (pintype "passive"))
    )
    (net (code "27") (name "Net-(DA1A-OUT)") (class "Default")
      (node (ref "DA1") (pin "6") (pinfunction "OUT_6") (pintype "output"))
      (node (ref "R1") (pin "2") (pinfunction "2_2") (pintype "passive"))
      (node (ref "R3") (pin "2") (pinfunction "2_2") (pintype "passive"))
    )
    (net (code "28") (name "Net-(DA1A-V+)") (class "Default")
      (node (ref "C1") (pin "2") (pinfunction "2_2") (pintype "passive"))
      (node (ref "C47") (pin "2") (pinfunction "2_2") (pintype "passive"))
      (node (ref "C48") (pin "2") (pinfunction "2_2") (pintype "passive"))
      (node (ref "DA1") (pin "7") (pinfunction "V+_7") (pintype "power_in"))
      (node (ref "L1") (pin "2") (pinfunction "2_2") (pintype "passive"))
    )
    (net (code "29") (name "Net-(DA1A-V-)") (class "Default")
      (node (ref "C2") (pin "2") (pinfunction "2_2") (pintype "passive"))
      (node (ref "C49") (pin "2") (pinfunction "2_2") (pintype "passive"))
      (node (ref "C50") (pin "2") (pinfunction "2_2") (pintype "passive"))
      (node (ref "DA1") (pin "4") (pinfunction "V-_4") (pintype "power_in"))
      (node (ref "L2") (pin "2") (pinfunction "2_2") (pintype "passive"))
    )
    (net (code "30") (name "Net-(DA2A-IN+)") (class "Default")
      (node (ref "DA2") (pin "3") (pinfunction "IN+_3") (pintype "input"))
      (node (ref "R13") (pin "2") (pinfunction "2_2") (pintype "passive"))
      (node (ref "R17") (pin "1") (pinfunction "1_1") (pintype "passive"))
    )
    (net (code "31") (name "Net-(DA2A-IN-)") (class "Default")
      (node (ref "DA2") (pin "2") (pinfunction "IN-_2") (pintype "input"))
      (node (ref "R7") (pin "2") (pinfunction "2_2") (pintype "passive"))
      (node (ref "R8") (pin "1") (pinfunction "1_1") (pintype "passive"))
    )
    (net (code "32") (name "Net-(DA2A-OUT)") (class "Default")
      (node (ref "DA2") (pin "6") (pinfunction "OUT_6") (pintype "output"))
      (node (ref "R12") (pin "2") (pinfunction "2_2") (pintype "passive"))
      (node (ref "R8") (pin "2") (pinfunction "2_2") (pintype "passive"))
    )
    (net (code "33") (name "Net-(DA2A-V+)") (class "Default")
      (node (ref "C5") (pin "2") (pinfunction "2_2") (pintype "passive"))
      (node (ref "C51") (pin "1") (pinfunction "1_1") (pintype "passive"))
      (node (ref "C52") (pin "1") (pinfunction "1_1") (pintype "passive"))
      (node (ref "DA2") (pin "7") (pinfunction "V+_7") (pintype "power_in"))
      (node (ref "L3") (pin "2") (pinfunction "2_2") (pintype "passive"))
    )
    (net (code "34") (name "Net-(DA2A-V-)") (class "Default")
      (node (ref "C14") (pin "2") (pinfunction "2_2") (pintype "passive"))
      (node (ref "C53") (pin "1") (pinfunction "1_1") (pintype "passive"))
      (node (ref "C54") (pin "1") (pinfunction "1_1") (pintype "passive"))
      (node (ref "DA2") (pin "4") (pinfunction "V-_4") (pintype "power_in"))
      (node (ref "L4") (pin "2") (pinfunction "2_2") (pintype "passive"))
    )
    (net (code "35") (name "Net-(DA3-SYNCIN)") (class "Default")
      (node (ref "DA3") (pin "14") (pinfunction "SYNCIN_14") (pintype "input"))
      (node (ref "R16") (pin "1") (pinfunction "1_1") (pintype "passive"))
    )
    (net (code "36") (name "Net-(DA3-VOUT+)") (class "Default")
      (node (ref "C31") (pin "2") (pinfunction "2_2") (pintype "passive"))
      (node (ref "C32") (pin "2") (pinfunction "2_2") (pintype "passive"))
      (node (ref "DA3") (pin "6") (pinfunction "VOUT+_6") (pintype "output"))
      (node (ref "L6") (pin "1") (pinfunction "1_1") (pintype "passive"))
    )
    (net (code "37") (name "Net-(DA3-VOUT-)") (class "Default")
      (node (ref "C35") (pin "2") (pinfunction "2_2") (pintype "passive"))
      (node (ref "C36") (pin "2") (pinfunction "2_2") (pintype "passive"))
      (node (ref "DA3") (pin "7") (pinfunction "VOUT-_7") (pintype "output"))
      (node (ref "L7") (pin "1") (pinfunction "1_1") (pintype "passive"))
    )
    (net (code "38") (name "Net-(DA3-VS+)") (class "Default")
      (node (ref "C29") (pin "2") (pinfunction "2_2") (pintype "passive"))
      (node (ref "C30") (pin "2") (pinfunction "2_2") (pintype "passive"))
      (node (ref "DA3") (pin "1") (pinfunction "VS+_1") (pintype "input"))
      (node (ref "L5") (pin "2") (pinfunction "2_2") (pintype "passive"))
    )
    (net (code "39") (name "Net-(DA4-ENABLE)") (class "Default")
      (node (ref "C42") (pin "2") (pinfunction "2_2") (pintype "passive"))
      (node (ref "DA4") (pin "1") (pinfunction "VIN_1") (pintype "power_in"))
      (node (ref "DA4") (pin "5") (pinfunction "ENABLE_5") (pintype "input"))
      (node (ref "L9") (pin "2") (pinfunction "2_2") (pintype "passive"))
    )
    (net (code "40") (name "Net-(DA4-NR{slash}ADJUST)") (class "Default")
      (node (ref "C43") (pin "2") (pinfunction "2_2") (pintype "passive"))
      (node (ref "DA4") (pin "4") (pinfunction "NR/ADJUST_4") (pintype "input"))
      (node (ref "R22") (pin "1") (pinfunction "1_1") (pintype "passive"))
      (node (ref "R24") (pin "2") (pinfunction "2_2") (pintype "passive"))
      (node (ref "R25") (pin "2") (pinfunction "2_2") (pintype "passive"))
    )
    (net (code "41") (name "Net-(DA4-VOUT)") (class "Default")
      (node (ref "C40") (pin "2") (pinfunction "2_2") (pintype "passive"))
      (node (ref "DA4") (pin "2") (pinfunction "VOUT_2") (pintype "power_in"))
      (node (ref "R21") (pin "1") (pinfunction "1_1") (pintype "passive"))
      (node (ref "R22") (pin "2") (pinfunction "2_2") (pintype "passive"))
    )
    (net (code "42") (name "Net-(DD1A-*CH0_IOUT)") (class "Default")
      (node (ref "DD1") (pin "9") (pinfunction "*CH0_IOUT_9") (pintype "output"))
      (node (ref "R2") (pin "1") (pinfunction "1_1") (pintype "passive"))
      (node (ref "R4") (pin "2") (pinfunction "2_2") (pintype "passive"))
    )
    (net (code "43") (name "Net-(DD1A-*CH1_OUT)") (class "Default")
      (node (ref "DD1") (pin "14") (pinfunction "*CH1_OUT_14") (pintype "output"))
      (node (ref "R7") (pin "1") (pinfunction "1_1") (pintype "passive"))
      (node (ref "R9") (pin "2") (pinfunction "2_2") (pintype "passive"))
    )
    (net (code "44") (name "Net-(DD1A-*CS)") (class "Default")
      (node (ref "DD1") (pin "47") (pinfunction "*CS_47") (pintype "input"))
      (node (ref "R27") (pin "1") (pinfunction "1_1") (pintype "passive"))
    )
    (net (code "45") (name "Net-(DD1A-*REF_CLK)") (class "Default")
      (node (ref "C21") (pin "2") (pinfunction "2_2") (pintype "passive"))
      (node (ref "DD1") (pin "22") (pinfunction "*REF_CLK_22") (pintype "input"))
      (node (ref "Q1") (pin "1") (pinfunction "1_1") (pintype "passive"))
    )
    (net (code "46") (name "Net-(DD1A-CH0_IOUT)") (class "Default")
      (node (ref "DD1") (pin "8") (pinfunction "CH0_IOUT_8") (pintype "output"))
      (node (ref "R4") (pin "1") (pinfunction "1_1") (pintype "passive"))
      (node (ref "R5") (pin "1") (pinfunction "1_1") (pintype "passive"))
    )
    (net (code "47") (name "Net-(DD1A-CH1_OUT)") (class "Default")
      (node (ref "DD1") (pin "13") (pinfunction "CH1_OUT_13") (pintype "output"))
      (node (ref "R13") (pin "1") (pinfunction "1_1") (pintype "passive"))
      (node (ref "R9") (pin "1") (pinfunction "1_1") (pintype "passive"))
    )
    (net (code "48") (name "Net-(DD1A-CLK_MODE_SEL)") (class "Default")
      (node (ref "DD1") (pin "24") (pinfunction "CLK_MODE_SEL_24") (pintype "input"))
      (node (ref "R20") (pin "1") (pinfunction "1_1") (pintype "passive"))
    )
    (net (code "49") (name "Net-(DD1A-DAC_RSET)") (class "Default")
      (node (ref "DD1") (pin "17") (pinfunction "DAC_RSET_17") (pintype "input"))
      (node (ref "R18") (pin "2") (pinfunction "2_2") (pintype "passive"))
    )
    (net (code "50") (name "Net-(DD1A-I{slash}O_UPDATE)") (class "Default")
      (node (ref "DD1") (pin "46") (pinfunction "I/O_UPDATE_46") (pintype "input"))
      (node (ref "R26") (pin "1") (pinfunction "1_1") (pintype "passive"))
    )
    (net (code "51") (name "Net-(DD1A-LOOP_FILTER)") (class "Default")
      (node (ref "DD1") (pin "27") (pinfunction "LOOP_FILTER_27") (pintype "input"))
      (node (ref "R19") (pin "2") (pinfunction "2_2") (pintype "passive"))
    )
    (net (code "52") (name "Net-(DD1A-MASTER_RESET)") (class "Default")
      (node (ref "DD1") (pin "3") (pinfunction "MASTER_RESET_3") (pintype "input"))
      (node (ref "R31") (pin "1") (pinfunction "1_1") (pintype "passive"))
    )
    (net (code "53") (name "Net-(DD1A-P0)") (class "Default")
      (node (ref "DD1") (pin "40") (pinfunction "P0_40") (pintype "input"))
      (node (ref "R34") (pin "1") (pinfunction "1_1") (pintype "passive"))
    )
    (net (code "54") (name "Net-(DD1A-P1)") (class "Default")
      (node (ref "DD1") (pin "41") (pinfunction "P1_41") (pintype "input"))
      (node (ref "R35") (pin "1") (pinfunction "1_1") (pintype "passive"))
    )
    (net (code "55") (name "Net-(DD1A-P2)") (class "Default")
      (node (ref "DD1") (pin "42") (pinfunction "P2_42") (pintype "input"))
      (node (ref "R36") (pin "1") (pinfunction "1_1") (pintype "passive"))
    )
    (net (code "56") (name "Net-(DD1A-P3)") (class "Default")
      (node (ref "DD1") (pin "43") (pinfunction "P3_43") (pintype "input"))
      (node (ref "R37") (pin "1") (pinfunction "1_1") (pintype "passive"))
    )
    (net (code "57") (name "Net-(DD1A-REF_CLK)") (class "Default")
      (node (ref "C20") (pin "2") (pinfunction "2_2") (pintype "passive"))
      (node (ref "DD1") (pin "23") (pinfunction "REF_CLK_23") (pintype "input"))
      (node (ref "Q1") (pin "2") (pinfunction "2_2") (pintype "passive"))
    )
    (net (code "58") (name "Net-(DD1A-SCLK)") (class "Default")
      (node (ref "DD1") (pin "48") (pinfunction "SCLK_48") (pintype "input"))
      (node (ref "R30") (pin "1") (pinfunction "1_1") (pintype "passive"))
    )
    (net (code "59") (name "Net-(DD1A-SDIO_0)") (class "Default")
      (node (ref "DD1") (pin "50") (pinfunction "SDIO_0_50") (pintype "bidirectional"))
      (node (ref "R28") (pin "1") (pinfunction "1_1") (pintype "passive"))
    )
    (net (code "60") (name "Net-(DD1A-SDIO_1)") (class "Default")
      (node (ref "DD1") (pin "51") (pinfunction "SDIO_1_51") (pintype "bidirectional"))
      (node (ref "R32") (pin "1") (pinfunction "1_1") (pintype "passive"))
    )
    (net (code "61") (name "Net-(DD1A-SDIO_2)") (class "Default")
      (node (ref "DD1") (pin "52") (pinfunction "SDIO_2_52") (pintype "bidirectional"))
      (node (ref "R29") (pin "1") (pinfunction "1_1") (pintype "passive"))
    )
    (net (code "62") (name "Net-(DD1A-SDIO_3)") (class "Default")
      (node (ref "DD1") (pin "53") (pinfunction "SDIO_3_53") (pintype "bidirectional"))
      (node (ref "R33") (pin "1") (pinfunction "1_1") (pintype "passive"))
    )
    (net (code "63") (name "Net-(DD1A-SYNC_CLK)") (class "Default")
      (node (ref "DD1") (pin "54") (pinfunction "SYNC_CLK_54") (pintype "output"))
      (node (ref "J3") (pin "1") (pinfunction "1_1") (pintype "passive"))
      (node (ref "R15") (pin "1") (pinfunction "1_1") (pintype "passive"))
    )
    (net (code "64") (name "Net-(DD1A-SYNC_IN)") (class "Default")
      (node (ref "DD1") (pin "1") (pinfunction "SYNC_IN_1") (pintype "input"))
      (node (ref "J1") (pin "1") (pinfunction "1_1") (pintype "passive"))
      (node (ref "R14") (pin "1") (pinfunction "1_1") (pintype "passive"))
    )
    (net (code "65") (name "Net-(DD1A-SYNC_OUT)") (class "Default")
      (node (ref "DD1") (pin "2") (pinfunction "SYNC_OUT_2") (pintype "output"))
      (node (ref "J2") (pin "1") (pinfunction "1_1") (pintype "passive"))
    )
    (net (code "66") (name "Net-(J4-Pad1)") (class "Default")
      (node (ref "J4") (pin "1") (pinfunction "1_1") (pintype "passive"))
      (node (ref "R3") (pin "1") (pinfunction "1_1") (pintype "passive"))
      (node (ref "X3") (pin "1") (pinfunction "1_1") (pintype "passive"))
    )
    (net (code "67") (name "Net-(J5-Pad1)") (class "Default")
      (node (ref "J5") (pin "1") (pinfunction "1_1") (pintype "passive"))
      (node (ref "R12") (pin "1") (pinfunction "1_1") (pintype "passive"))
      (node (ref "X4") (pin "1") (pinfunction "1_1") (pintype "passive"))
    )
    (net (code "68") (name "Net-(L10-Pad1)") (class "Default")
      (node (ref "L10") (pin "1") (pinfunction "1_1") (pintype "passive"))
      (node (ref "L8") (pin "1") (pinfunction "1_1") (pintype "passive"))
      (node (ref "R21") (pin "2") (pinfunction "2_2") (pintype "passive"))
    )
    (net (code "69") (name "Net-(VD1-Anode)") (class "Default")
      (node (ref "R23") (pin "1") (pinfunction "1_1") (pintype "passive"))
      (node (ref "VD1") (pin "2") (pinfunction "Anode_2") (pintype "passive"))
    )
    (net (code "70") (name "unconnected-(DA1B-NC-Pad1)") (class "Default")
      (node (ref "DA1") (pin "1") (pinfunction "NC_1") (pintype "passive"))
    )
    (net (code "71") (name "unconnected-(DA1B-NC-Pad5)") (class "Default")
      (node (ref "DA1") (pin "5") (pinfunction "NC_5") (pintype "passive"))
    )
    (net (code "72") (name "unconnected-(DA1B-NC-Pad8)") (class "Default")
      (node (ref "DA1") (pin "8") (pinfunction "NC_8") (pintype "passive"))
    )
    (net (code "73") (name "unconnected-(DA2B-NC-Pad1)") (class "Default")
      (node (ref "DA2") (pin "1") (pinfunction "NC_1") (pintype "passive"))
    )
    (net (code "74") (name "unconnected-(DA2B-NC-Pad5)") (class "Default")
      (node (ref "DA2") (pin "5") (pinfunction "NC_5") (pintype "passive"))
    )
    (net (code "75") (name "unconnected-(DA2B-NC-Pad8)") (class "Default")
      (node (ref "DA2") (pin "8") (pinfunction "NC_8") (pintype "passive"))
    )
    (net (code "76") (name "unconnected-(DA3-SYNCOUT-Pad8)") (class "Default")
      (node (ref "DA3") (pin "8") (pinfunction "SYNCOUT_8") (pintype "output+no_connect"))
    )
    (net (code "77") (name "unconnected-(DD1B-NC-Pad28)") (class "Default")
      (node (ref "DD1") (pin "28") (pinfunction "NC_28") (pintype "passive"))
    )
    (net (code "78") (name "unconnected-(DD1B-NC-Pad32)") (class "Default")
      (node (ref "DD1") (pin "32") (pinfunction "NC_32") (pintype "passive"))
    )
    (net (code "79") (name "unconnected-(DD1B-NC-Pad34)") (class "Default")
      (node (ref "DD1") (pin "34") (pinfunction "NC_34") (pintype "passive"))
    )
    (net (code "80") (name "unconnected-(DD1B-NC-Pad38)") (class "Default")
      (node (ref "DD1") (pin "38") (pinfunction "NC_38") (pintype "passive"))
    )
    (net (code "81") (name "unconnected-(X1-Pad3)") (class "Default")
      (node (ref "X1") (pin "3") (pinfunction "3_3") (pintype "passive"))
    )
    (net (code "82") (name "unconnected-(X1-Pad6)") (class "Default")
      (node (ref "X1") (pin "6") (pinfunction "6_6") (pintype "passive"))
    )
    (net (code "83") (name "unconnected-(X1-Pad8)") (class "Default")
      (node (ref "X1") (pin "8") (pinfunction "8_8") (pintype "passive"))
    )
    (net (code "84") (name "unconnected-(X1-Pad10)") (class "Default")
      (node (ref "X1") (pin "10") (pinfunction "10_10") (pintype "passive"))
    )
    (net (code "85") (name "unconnected-(X1-Pad12)") (class "Default")
      (node (ref "X1") (pin "12") (pinfunction "12_12") (pintype "passive"))
    )
    (net (code "86") (name "unconnected-(X1-Pad14)") (class "Default")
      (node (ref "X1") (pin "14") (pinfunction "14_14") (pintype "passive"))
    )
    (net (code "87") (name "unconnected-(X1-Pad16)") (class "Default")
      (node (ref "X1") (pin "16") (pinfunction "16_16") (pintype "passive"))
    )
    (net (code "88") (name "unconnected-(X1-Pad18)") (class "Default")
      (node (ref "X1") (pin "18") (pinfunction "18_18") (pintype "passive"))
    )
    (net (code "89") (name "unconnected-(X2-Pad6)") (class "Default")
      (node (ref "X2") (pin "6") (pinfunction "6_6") (pintype "passive+no_connect"))
    )
    (net (code "90") (name "unconnected-(X2-Pad7)") (class "Default")
      (node (ref "X2") (pin "7") (pinfunction "7_7") (pintype "passive+no_connect"))
    )
    (net (code "91") (name "unconnected-(X2-Pad8)") (class "Default")
      (node (ref "X2") (pin "8") (pinfunction "8_8") (pintype "passive+no_connect"))
    )
    (net (code "92") (name "unconnected-(X2-Pad9)") (class "Default")
      (node (ref "X2") (pin "9") (pinfunction "9_9") (pintype "passive+no_connect"))
    )
    (net (code "93") (name "unconnected-(X2-Pad10)") (class "Default")
      (node (ref "X2") (pin "10") (pinfunction "10_10") (pintype "passive+no_connect"))
    )
    (net (code "94") (name "unconnected-(X2-Pad11)") (class "Default")
      (node (ref "X2") (pin "11") (pinfunction "11_11") (pintype "passive+no_connect"))
    )
    (net (code "95") (name "unconnected-(X2-Pad12)") (class "Default")
      (node (ref "X2") (pin "12") (pinfunction "12_12") (pintype "passive+no_connect"))
    )
    (net (code "96") (name "unconnected-(X2-Pad13)") (class "Default")
      (node (ref "X2") (pin "13") (pinfunction "13_13") (pintype "passive+no_connect"))
    )
    (net (code "97") (name "unconnected-(X2-Pad14)") (class "Default")
      (node (ref "X2") (pin "14") (pinfunction "14_14") (pintype "passive+no_connect"))
    )
    (net (code "98") (name "unconnected-(X2-Pad15)") (class "Default")
      (node (ref "X2") (pin "15") (pinfunction "15_15") (pintype "passive+no_connect"))
    )
    (net (code "99") (name "unconnected-(X2-Pad16)") (class "Default")
      (node (ref "X2") (pin "16") (pinfunction "16_16") (pintype "passive+no_connect"))
    )
    (net (code "100") (name "unconnected-(X2-Pad17)") (class "Default")
      (node (ref "X2") (pin "17") (pinfunction "17_17") (pintype "passive"))
    )
    (net (code "101") (name "unconnected-(X2-Pad18)") (class "Default")
      (node (ref "X2") (pin "18") (pinfunction "18_18") (pintype "passive"))
    )
    (net (code "102") (name "unconnected-(X2-Pad19)") (class "Default")
      (node (ref "X2") (pin "19") (pinfunction "19_19") (pintype "passive"))
    )
    (net (code "103") (name "unconnected-(X2-Pad20)") (class "Default")
      (node (ref "X2") (pin "20") (pinfunction "20_20") (pintype "passive"))
    )
    (net (code "104") (name "unconnected-(X2-Pad21)") (class "Default")
      (node (ref "X2") (pin "21") (pinfunction "21_21") (pintype "passive"))
    )
    (net (code "105") (name "unconnected-(X2-Pad22)") (class "Default")
      (node (ref "X2") (pin "22") (pinfunction "22_22") (pintype "passive"))
    )
    (net (code "106") (name "unconnected-(X2-Pad23)") (class "Default")
      (node (ref "X2") (pin "23") (pinfunction "23_23") (pintype "passive"))
    )
    (net (code "107") (name "unconnected-(X2-Pad24)") (class "Default")
      (node (ref "X2") (pin "24") (pinfunction "24_24") (pintype "passive"))
    )
  )
)
